# Programmer_Board.net
KiCad netlist of a schematic drawn in EAGLE
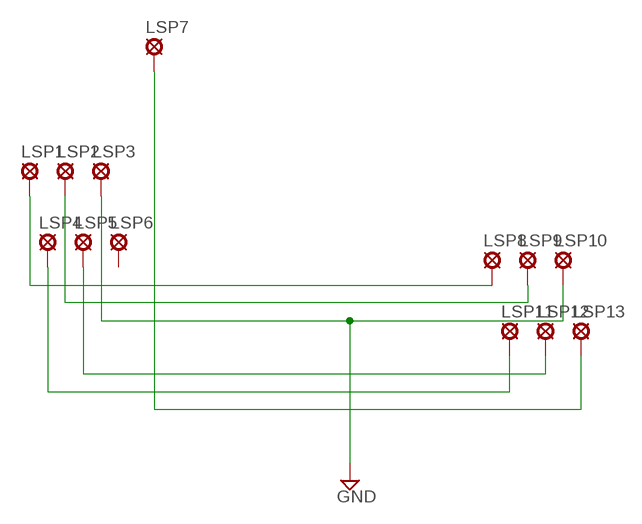
[diagram p0: schematic, sheet 1]

(export (version "E")
  (design (tool "Eeschema 10.0.6"))
  (components
    (comp (ref "LSP1")
      (value "LSP10_CLSP10_C")
      (footprint "eagle-import:LSP10_C")
      (libsource (lib "eagle-import") (part "LSP10_CLSP10_C"))
    )
    (comp (ref "LSP2")
      (value "LSP10_CLSP10_C")
      (footprint "eagle-import:LSP10_C")
      (libsource (lib "eagle-import") (part "LSP10_CLSP10_C"))
    )
    (comp (ref "LSP3")
      (value "LSP10_CLSP10_C")
      (footprint "eagle-import:LSP10_C")
      (libsource (lib "eagle-import") (part "LSP10_CLSP10_C"))
    )
    (comp (ref "LSP4")
      (value "LSP10_CLSP10_C")
      (footprint "eagle-import:LSP10_C")
      (libsource (lib "eagle-import") (part "LSP10_CLSP10_C"))
    )
    (comp (ref "LSP5")
      (value "LSP10_CLSP10_C")
      (footprint "eagle-import:LSP10_C")
      (libsource (lib "eagle-import") (part "LSP10_CLSP10_C"))
    )
    (comp (ref "LSP6")
      (value "LSP10_CLSP10_C")
      (footprint "eagle-import:LSP10_C")
      (libsource (lib "eagle-import") (part "LSP10_CLSP10_C"))
    )
    (comp (ref "LSP7")
      (value "LSP10_CLSP10_C")
      (footprint "eagle-import:LSP10_C")
      (libsource (lib "eagle-import") (part "LSP10_CLSP10_C"))
    )
    (comp (ref "LSP8")
      (value "LSP10_CLSP10_C")
      (footprint "eagle-import:LSP10_C")
      (libsource (lib "eagle-import") (part "LSP10_CLSP10_C"))
    )
    (comp (ref "LSP9")
      (value "LSP10_CLSP10_C")
      (footprint "eagle-import:LSP10_C")
      (libsource (lib "eagle-import") (part "LSP10_CLSP10_C"))
    )
    (comp (ref "LSP10")
      (value "LSP10_CLSP10_C")
      (footprint "eagle-import:LSP10_C")
      (libsource (lib "eagle-import") (part "LSP10_CLSP10_C"))
    )
    (comp (ref "LSP11")
      (value "LSP10_CLSP10_C")
      (footprint "eagle-import:LSP10_C")
      (libsource (lib "eagle-import") (part "LSP10_CLSP10_C"))
    )
    (comp (ref "LSP12")
      (value "LSP10_CLSP10_C")
      (footprint "eagle-import:LSP10_C")
      (libsource (lib "eagle-import") (part "LSP10_CLSP10_C"))
    )
    (comp (ref "LSP13")
      (value "LSP10_CLSP10_C")
      (footprint "eagle-import:LSP10_C")
      (libsource (lib "eagle-import") (part "LSP10_CLSP10_C"))
    )
  )
  (nets
    (net (code "1") (name "GND") (class "Default")
      (node (ref "LSP10") (pin "P$1") (pinfunction "MP_P$1") (pintype "passive"))
      (node (ref "LSP3") (pin "P$1") (pinfunction "MP_P$1") (pintype "passive"))
    )
    (net (code "2") (name "Net-(LSP1-MP)") (class "Default")
      (node (ref "LSP1") (pin "P$1") (pinfunction "MP_P$1") (pintype "passive"))
      (node (ref "LSP8") (pin "P$1") (pinfunction "MP_P$1") (pintype "passive"))
    )
    (net (code "3") (name "Net-(LSP2-MP)") (class "Default")
      (node (ref "LSP2") (pin "P$1") (pinfunction "MP_P$1") (pintype "passive"))
      (node (ref "LSP9") (pin "P$1") (pinfunction "MP_P$1") (pintype "passive"))
    )
    (net (code "4") (name "Net-(LSP11-MP)") (class "Default")
      (node (ref "LSP11") (pin "P$1") (pinfunction "MP_P$1") (pintype "passive"))
      (node (ref "LSP4") (pin "P$1") (pinfunction "MP_P$1") (pintype "passive"))
    )
    (net (code "5") (name "Net-(LSP12-MP)") (class "Default")
      (node (ref "LSP12") (pin "P$1") (pinfunction "MP_P$1") (pintype "passive"))
      (node (ref "LSP5") (pin "P$1") (pinfunction "MP_P$1") (pintype "passive"))
    )
    (net (code "6") (name "Net-(LSP13-MP)") (class "Default")
      (node (ref "LSP13") (pin "P$1") (pinfunction "MP_P$1") (pintype "passive"))
      (node (ref "LSP7") (pin "P$1") (pinfunction "MP_P$1") (pintype "passive"))
    )
    (net (code "7") (name "unconnected-(LSP6-MP-PadP$1)") (class "Default")
      (node (ref "LSP6") (pin "P$1") (pinfunction "MP_P$1") (pintype "passive"))
    )
  )
)
